# Controller_V1.net
KiCad netlist of a schematic drawn in EAGLE
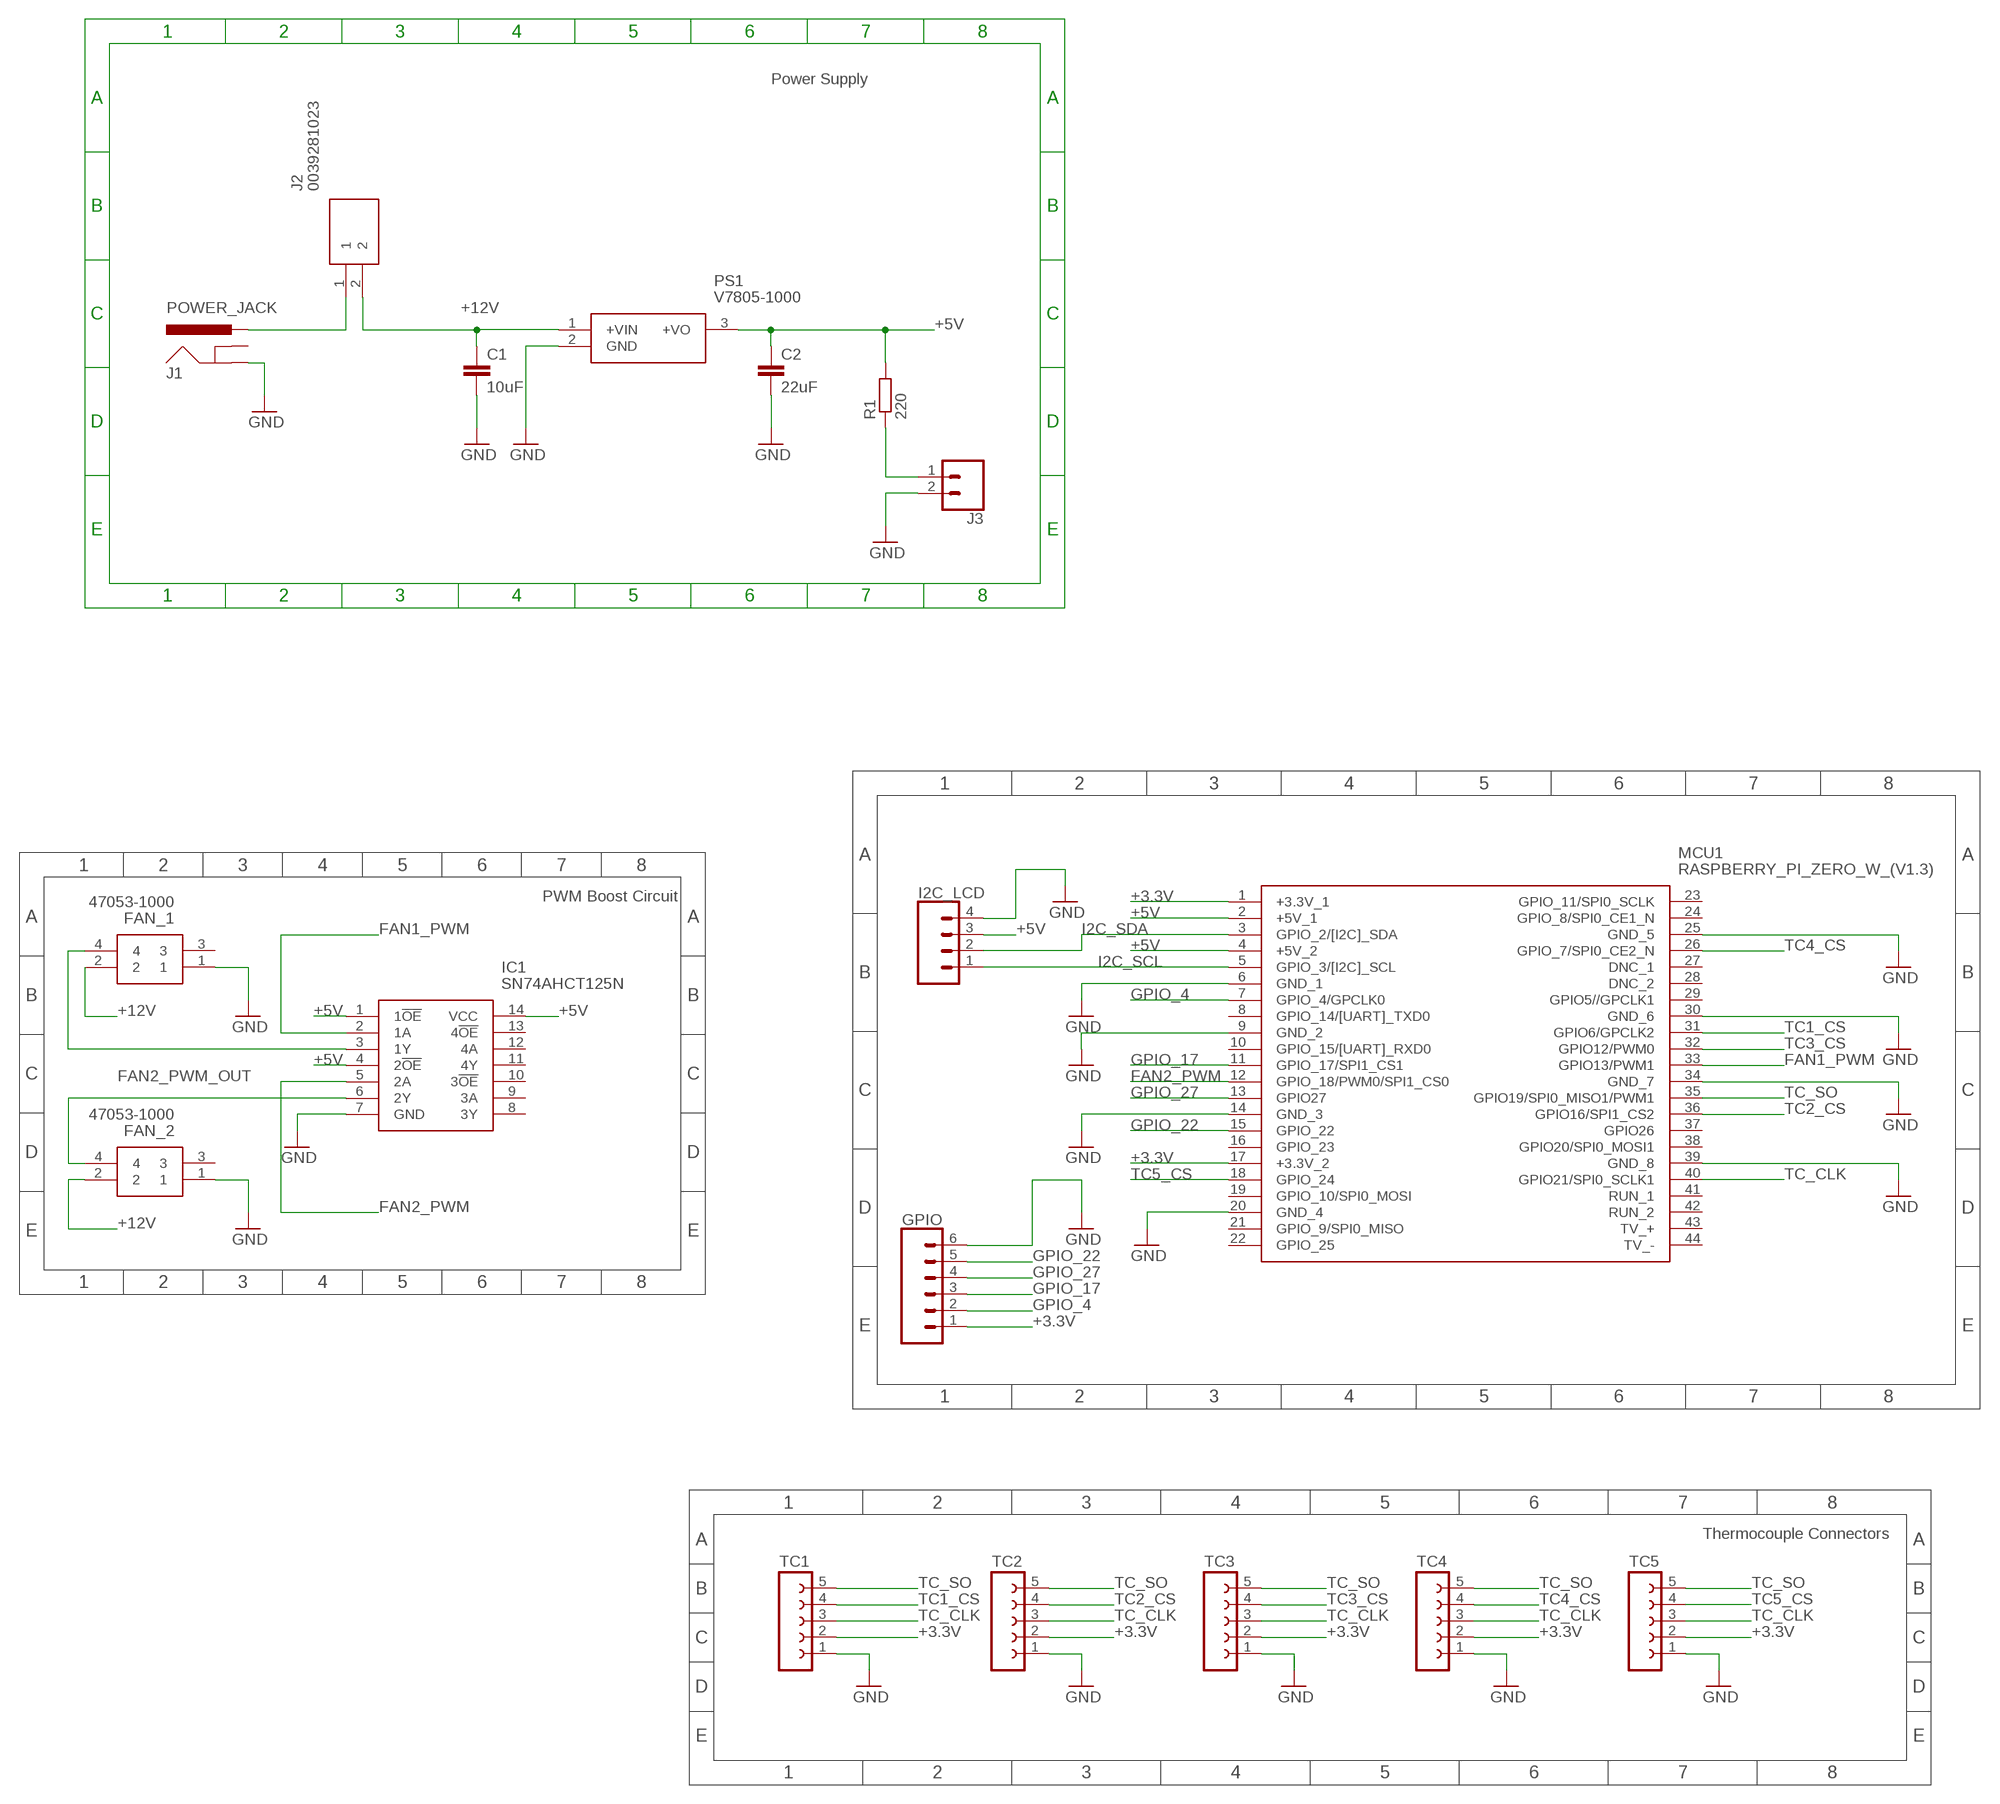
[diagram p0: schematic, sheet 1]

(export (version "E")
  (design (tool "Eeschema 10.0.6"))
  (components
    (comp (ref "C1")
      (value "10uF")
      (footprint "eagle-import:C050-024X044")
      (libsource (lib "eagle-import") (part "C-EU050-024X044"))
    )
    (comp (ref "C2")
      (value "22uF")
      (footprint "eagle-import:C050-024X044")
      (libsource (lib "eagle-import") (part "C-EU050-024X044"))
    )
    (comp (ref "FAN_1")
      (value "47053-1000")
      (footprint "eagle-import:47053-1000")
      (fields (field (name "MOUSER_PART_NUMBER") "538-47053-1000"))
      (libsource (lib "eagle-import") (part "47053-1000"))
    )
    (comp (ref "FAN_2")
      (value "47053-1000")
      (footprint "eagle-import:47053-1000")
      (fields (field (name "MOUSER_PART_NUMBER") "538-47053-1000"))
      (libsource (lib "eagle-import") (part "47053-1000"))
    )
    (comp (ref "GPIO")
      (value "CONN_06SILK_FEMALE_PTH")
      (footprint "eagle-import:1X06")
      (libsource (lib "eagle-import") (part "CONN_06SILK_FEMALE_PTH"))
    )
    (comp (ref "I2C_LCD")
      (value "CONN_04PTH")
      (footprint "eagle-import:1X04")
      (libsource (lib "eagle-import") (part "CONN_04PTH"))
    )
    (comp (ref "IC1")
      (value "SN74AHCT125N")
      (footprint "eagle-import:DIP794W53P254L1930H508Q14N")
      (fields (field (name "MOUSER_PART_NUMBER") "595-SN74AHCT125N"))
      (libsource (lib "eagle-import") (part "SN74AHCT125N"))
    )
    (comp (ref "J1")
      (value "POWER_JACK")
      (footprint "eagle-import:POWER_JACK_PTH")
      (libsource (lib "eagle-import") (part "POWER_JACK"))
    )
    (comp (ref "J2")
      (value "0039281023")
      (footprint "eagle-import:SHDR2W145P0X550_1X2_960X540X13")
      (libsource (lib "eagle-import") (part "0039281023"))
    )
    (comp (ref "J3")
      (value "CONN_02")
      (footprint "eagle-import:1X02")
      (libsource (lib "eagle-import") (part "CONN_02"))
    )
    (comp (ref "MCU1")
      (value "RASPBERRY_PI_ZERO_W_(V1.3)")
      (footprint "eagle-import:RASPBERRYPIZEROWV13")
      (fields (field (name "MANUFACTURER_PART_NUMBER") "Raspberry Pi Zero W (v1.3)"))
      (libsource (lib "eagle-import") (part "RASPBERRY_PI_ZERO_W_(V1.3)"))
    )
    (comp (ref "PS1")
      (value "V7805-1000")
      (footprint "eagle-import:V78031500")
      (fields (field (name "MOUSER_PART_NUMBER") "490-V7805-1000"))
      (libsource (lib "eagle-import") (part "V7805-1000"))
    )
    (comp (ref "R1")
      (value "220")
      (footprint "eagle-import:0309_10")
      (libsource (lib "eagle-import") (part "R-EU_0309/10"))
    )
    (comp (ref "TC1")
      (value "FE05-1")
      (footprint "eagle-import:FE05-1")
      (libsource (lib "eagle-import") (part "FE05-1"))
    )
    (comp (ref "TC2")
      (value "FE05-1")
      (footprint "eagle-import:FE05-1")
      (libsource (lib "eagle-import") (part "FE05-1"))
    )
    (comp (ref "TC3")
      (value "FE05-1")
      (footprint "eagle-import:FE05-1")
      (libsource (lib "eagle-import") (part "FE05-1"))
    )
    (comp (ref "TC4")
      (value "FE05-1")
      (footprint "eagle-import:FE05-1")
      (libsource (lib "eagle-import") (part "FE05-1"))
    )
    (comp (ref "TC5")
      (value "FE05-1")
      (footprint "eagle-import:FE05-1")
      (libsource (lib "eagle-import") (part "FE05-1"))
    )
  )
  (nets
    (net (code "1") (name "/+3.3V") (class "Default")
      (node (ref "GPIO") (pin "1") (pinfunction "1_1") (pintype "passive"))
      (node (ref "MCU1") (pin "1") (pinfunction "+3.3V_1_1") (pintype "bidirectional"))
      (node (ref "MCU1") (pin "17") (pinfunction "+3.3V_2_17") (pintype "bidirectional"))
      (node (ref "TC1") (pin "2") (pinfunction "2_2") (pintype "passive"))
      (node (ref "TC2") (pin "2") (pinfunction "2_2") (pintype "passive"))
      (node (ref "TC3") (pin "2") (pinfunction "2_2") (pintype "passive"))
      (node (ref "TC4") (pin "2") (pinfunction "2_2") (pintype "passive"))
      (node (ref "TC5") (pin "2") (pinfunction "2_2") (pintype "passive"))
    )
    (net (code "2") (name "/+5V") (class "Default")
      (node (ref "C2") (pin "1") (pinfunction "1_1") (pintype "passive"))
      (node (ref "I2C_LCD") (pin "3") (pinfunction "3_3") (pintype "passive"))
      (node (ref "IC1") (pin "1") (pinfunction "1~{OE}_1") (pintype "bidirectional"))
      (node (ref "IC1") (pin "14") (pinfunction "VCC_14") (pintype "bidirectional"))
      (node (ref "IC1") (pin "4") (pinfunction "2~{OE}_4") (pintype "bidirectional"))
      (node (ref "MCU1") (pin "2") (pinfunction "+5V_1_2") (pintype "bidirectional"))
      (node (ref "MCU1") (pin "4") (pinfunction "+5V_2_4") (pintype "bidirectional"))
      (node (ref "PS1") (pin "3") (pinfunction "+VO_3") (pintype "bidirectional"))
      (node (ref "R1") (pin "2") (pinfunction "2_2") (pintype "passive"))
    )
    (net (code "3") (name "/+12V") (class "Default")
      (node (ref "C1") (pin "1") (pinfunction "1_1") (pintype "passive"))
      (node (ref "FAN_1") (pin "2") (pinfunction "2_2") (pintype "bidirectional"))
      (node (ref "FAN_2") (pin "2") (pinfunction "2_2") (pintype "bidirectional"))
      (node (ref "J2") (pin "2") (pinfunction "2_2") (pintype "bidirectional"))
      (node (ref "PS1") (pin "1") (pinfunction "+VIN_1") (pintype "power_in"))
    )
    (net (code "4") (name "/FAN1_PWM") (class "Default")
      (node (ref "IC1") (pin "2") (pinfunction "1A_2") (pintype "bidirectional"))
      (node (ref "MCU1") (pin "33") (pinfunction "GPIO13/PWM1_33") (pintype "bidirectional"))
    )
    (net (code "5") (name "/FAN2_PWM") (class "Default")
      (node (ref "IC1") (pin "5") (pinfunction "2A_5") (pintype "bidirectional"))
      (node (ref "MCU1") (pin "12") (pinfunction "GPIO_18/PWM0/SPI1_CS0_12") (pintype "bidirectional"))
    )
    (net (code "6") (name "/FAN2_PWM_OUT") (class "Default")
      (node (ref "FAN_2") (pin "4") (pinfunction "4_4") (pintype "bidirectional"))
      (node (ref "IC1") (pin "6") (pinfunction "2Y_6") (pintype "bidirectional"))
    )
    (net (code "7") (name "/GPIO_4") (class "Default")
      (node (ref "GPIO") (pin "2") (pinfunction "2_2") (pintype "passive"))
      (node (ref "MCU1") (pin "7") (pinfunction "GPIO_4/GPCLK0_7") (pintype "bidirectional"))
    )
    (net (code "8") (name "/GPIO_17") (class "Default")
      (node (ref "GPIO") (pin "3") (pinfunction "3_3") (pintype "passive"))
      (node (ref "MCU1") (pin "11") (pinfunction "GPIO_17/SPI1_CS1_11") (pintype "bidirectional"))
    )
    (net (code "9") (name "/GPIO_22") (class "Default")
      (node (ref "GPIO") (pin "5") (pinfunction "5_5") (pintype "passive"))
      (node (ref "MCU1") (pin "15") (pinfunction "GPIO_22_15") (pintype "bidirectional"))
    )
    (net (code "10") (name "/GPIO_27") (class "Default")
      (node (ref "GPIO") (pin "4") (pinfunction "4_4") (pintype "passive"))
      (node (ref "MCU1") (pin "13") (pinfunction "GPIO27_13") (pintype "bidirectional"))
    )
    (net (code "11") (name "/I2C_SCL") (class "Default")
      (node (ref "I2C_LCD") (pin "1") (pinfunction "1_1") (pintype "passive"))
      (node (ref "MCU1") (pin "5") (pinfunction "GPIO_3/[I2C]_SCL_5") (pintype "bidirectional"))
    )
    (net (code "12") (name "/I2C_SDA") (class "Default")
      (node (ref "I2C_LCD") (pin "2") (pinfunction "2_2") (pintype "passive"))
      (node (ref "MCU1") (pin "3") (pinfunction "GPIO_2/[I2C]_SDA_3") (pintype "bidirectional"))
    )
    (net (code "13") (name "/TC1_CS") (class "Default")
      (node (ref "MCU1") (pin "31") (pinfunction "GPIO6/GPCLK2_31") (pintype "bidirectional"))
      (node (ref "TC1") (pin "4") (pinfunction "4_4") (pintype "passive"))
    )
    (net (code "14") (name "/TC2_CS") (class "Default")
      (node (ref "MCU1") (pin "36") (pinfunction "GPIO16/SPI1_CS2_36") (pintype "bidirectional"))
      (node (ref "TC2") (pin "4") (pinfunction "4_4") (pintype "passive"))
    )
    (net (code "15") (name "/TC3_CS") (class "Default")
      (node (ref "MCU1") (pin "32") (pinfunction "GPIO12/PWM0_32") (pintype "bidirectional"))
      (node (ref "TC3") (pin "4") (pinfunction "4_4") (pintype "passive"))
    )
    (net (code "16") (name "/TC4_CS") (class "Default")
      (node (ref "MCU1") (pin "26") (pinfunction "GPIO_7/SPI0_CE2_N_26") (pintype "bidirectional"))
      (node (ref "TC4") (pin "4") (pinfunction "4_4") (pintype "passive"))
    )
    (net (code "17") (name "/TC5_CS") (class "Default")
      (node (ref "MCU1") (pin "18") (pinfunction "GPIO_24_18") (pintype "bidirectional"))
      (node (ref "TC5") (pin "4") (pinfunction "4_4") (pintype "passive"))
    )
    (net (code "18") (name "/TC_CLK") (class "Default")
      (node (ref "MCU1") (pin "40") (pinfunction "GPIO21/SPI0_SCLK1_40") (pintype "bidirectional"))
      (node (ref "TC1") (pin "3") (pinfunction "3_3") (pintype "passive"))
      (node (ref "TC2") (pin "3") (pinfunction "3_3") (pintype "passive"))
      (node (ref "TC3") (pin "3") (pinfunction "3_3") (pintype "passive"))
      (node (ref "TC4") (pin "3") (pinfunction "3_3") (pintype "passive"))
      (node (ref "TC5") (pin "3") (pinfunction "3_3") (pintype "passive"))
    )
    (net (code "19") (name "/TC_SO") (class "Default")
      (node (ref "MCU1") (pin "35") (pinfunction "GPIO19/SPI0_MISO1/PWM1_35") (pintype "bidirectional"))
      (node (ref "TC1") (pin "5") (pinfunction "5_5") (pintype "passive"))
      (node (ref "TC2") (pin "5") (pinfunction "5_5") (pintype "passive"))
      (node (ref "TC3") (pin "5") (pinfunction "5_5") (pintype "passive"))
      (node (ref "TC4") (pin "5") (pinfunction "5_5") (pintype "passive"))
      (node (ref "TC5") (pin "5") (pinfunction "5_5") (pintype "passive"))
    )
    (net (code "20") (name "GND") (class "Default")
      (node (ref "C1") (pin "2") (pinfunction "2_2") (pintype "passive"))
      (node (ref "C2") (pin "2") (pinfunction "2_2") (pintype "passive"))
      (node (ref "FAN_1") (pin "1") (pinfunction "1_1") (pintype "bidirectional"))
      (node (ref "FAN_2") (pin "1") (pinfunction "1_1") (pintype "bidirectional"))
      (node (ref "GPIO") (pin "6") (pinfunction "6_6") (pintype "passive"))
      (node (ref "I2C_LCD") (pin "4") (pinfunction "4_4") (pintype "passive"))
      (node (ref "IC1") (pin "7") (pinfunction "GND_7") (pintype "bidirectional"))
      (node (ref "J1") (pin "GND") (pinfunction "GND_GND") (pintype "bidirectional"))
      (node (ref "J3") (pin "2") (pinfunction "2_2") (pintype "passive"))
      (node (ref "MCU1") (pin "14") (pinfunction "GND_3_14") (pintype "bidirectional"))
      (node (ref "MCU1") (pin "20") (pinfunction "GND_4_20") (pintype "bidirectional"))
      (node (ref "MCU1") (pin "25") (pinfunction "GND_5_25") (pintype "bidirectional"))
      (node (ref "MCU1") (pin "30") (pinfunction "GND_6_30") (pintype "bidirectional"))
      (node (ref "MCU1") (pin "34") (pinfunction "GND_7_34") (pintype "bidirectional"))
      (node (ref "MCU1") (pin "39") (pinfunction "GND_8_39") (pintype "bidirectional"))
      (node (ref "MCU1") (pin "6") (pinfunction "GND_1_6") (pintype "bidirectional"))
      (node (ref "MCU1") (pin "9") (pinfunction "GND_2_9") (pintype "bidirectional"))
      (node (ref "PS1") (pin "2") (pinfunction "GND_2") (pintype "bidirectional"))
      (node (ref "TC1") (pin "1") (pinfunction "1_1") (pintype "passive"))
      (node (ref "TC2") (pin "1") (pinfunction "1_1") (pintype "passive"))
      (node (ref "TC3") (pin "1") (pinfunction "1_1") (pintype "passive"))
      (node (ref "TC4") (pin "1") (pinfunction "1_1") (pintype "passive"))
      (node (ref "TC5") (pin "1") (pinfunction "1_1") (pintype "passive"))
    )
    (net (code "21") (name "Net-(IC1-1Y)") (class "Default")
      (node (ref "FAN_1") (pin "4") (pinfunction "4_4") (pintype "bidirectional"))
      (node (ref "IC1") (pin "3") (pinfunction "1Y_3") (pintype "bidirectional"))
    )
    (net (code "22") (name "Net-(J1-PadPWR)") (class "Default")
      (node (ref "J1") (pin "PWR") (pinfunction "PWR_PWR") (pintype "bidirectional"))
      (node (ref "J2") (pin "1") (pinfunction "1_1") (pintype "bidirectional"))
    )
    (net (code "23") (name "Net-(J3-Pad1)") (class "Default")
      (node (ref "J3") (pin "1") (pinfunction "1_1") (pintype "passive"))
      (node (ref "R1") (pin "1") (pinfunction "1_1") (pintype "passive"))
    )
    (net (code "24") (name "unconnected-(FAN_1-Pad3)") (class "Default")
      (node (ref "FAN_1") (pin "3") (pinfunction "3_3") (pintype "bidirectional"))
    )
    (net (code "25") (name "unconnected-(FAN_2-Pad3)") (class "Default")
      (node (ref "FAN_2") (pin "3") (pinfunction "3_3") (pintype "bidirectional"))
    )
    (net (code "26") (name "unconnected-(IC1-3A-Pad9)") (class "Default")
      (node (ref "IC1") (pin "9") (pinfunction "3A_9") (pintype "bidirectional"))
    )
    (net (code "27") (name "unconnected-(IC1-3Y-Pad8)") (class "Default")
      (node (ref "IC1") (pin "8") (pinfunction "3Y_8") (pintype "bidirectional"))
    )
    (net (code "28") (name "unconnected-(IC1-3~{OE}-Pad10)") (class "Default")
      (node (ref "IC1") (pin "10") (pinfunction "3~{OE}_10") (pintype "bidirectional"))
    )
    (net (code "29") (name "unconnected-(IC1-4A-Pad12)") (class "Default")
      (node (ref "IC1") (pin "12") (pinfunction "4A_12") (pintype "bidirectional"))
    )
    (net (code "30") (name "unconnected-(IC1-4Y-Pad11)") (class "Default")
      (node (ref "IC1") (pin "11") (pinfunction "4Y_11") (pintype "bidirectional"))
    )
    (net (code "31") (name "unconnected-(IC1-4~{OE}-Pad13)") (class "Default")
      (node (ref "IC1") (pin "13") (pinfunction "4~{OE}_13") (pintype "bidirectional"))
    )
    (net (code "32") (name "unconnected-(J1-PadGNDBREAK)") (class "Default")
      (node (ref "J1") (pin "GNDBREAK") (pinfunction "GNDBREAK_GNDBREAK") (pintype "bidirectional"))
    )
    (net (code "33") (name "unconnected-(MCU1-DNC_1-Pad27)") (class "Default")
      (node (ref "MCU1") (pin "27") (pinfunction "DNC_1_27") (pintype "bidirectional"))
    )
    (net (code "34") (name "unconnected-(MCU1-DNC_2-Pad28)") (class "Default")
      (node (ref "MCU1") (pin "28") (pinfunction "DNC_2_28") (pintype "bidirectional"))
    )
    (net (code "35") (name "unconnected-(MCU1-GPIO5{slash}{slash}GPCLK1-Pad29)") (class "Default")
      (node (ref "MCU1") (pin "29") (pinfunction "GPIO5//GPCLK1_29") (pintype "bidirectional"))
    )
    (net (code "36") (name "unconnected-(MCU1-GPIO20{slash}SPI0_MOSI1-Pad38)") (class "Default")
      (node (ref "MCU1") (pin "38") (pinfunction "GPIO20/SPI0_MOSI1_38") (pintype "bidirectional"))
    )
    (net (code "37") (name "unconnected-(MCU1-GPIO26-Pad37)") (class "Default")
      (node (ref "MCU1") (pin "37") (pinfunction "GPIO26_37") (pintype "bidirectional"))
    )
    (net (code "38") (name "unconnected-(MCU1-GPIO_8{slash}SPI0_CE1_N-Pad24)") (class "Default")
      (node (ref "MCU1") (pin "24") (pinfunction "GPIO_8/SPI0_CE1_N_24") (pintype "bidirectional"))
    )
    (net (code "39") (name "unconnected-(MCU1-GPIO_9{slash}SPI0_MISO-Pad21)") (class "Default")
      (node (ref "MCU1") (pin "21") (pinfunction "GPIO_9/SPI0_MISO_21") (pintype "bidirectional"))
    )
    (net (code "40") (name "unconnected-(MCU1-GPIO_10{slash}SPI0_MOSI-Pad19)") (class "Default")
      (node (ref "MCU1") (pin "19") (pinfunction "GPIO_10/SPI0_MOSI_19") (pintype "bidirectional"))
    )
    (net (code "41") (name "unconnected-(MCU1-GPIO_11{slash}SPI0_SCLK-Pad23)") (class "Default")
      (node (ref "MCU1") (pin "23") (pinfunction "GPIO_11/SPI0_SCLK_23") (pintype "bidirectional"))
    )
    (net (code "42") (name "unconnected-(MCU1-GPIO_14{slash}[UART]_TXD0-Pad8)") (class "Default")
      (node (ref "MCU1") (pin "8") (pinfunction "GPIO_14/[UART]_TXD0_8") (pintype "bidirectional"))
    )
    (net (code "43") (name "unconnected-(MCU1-GPIO_15{slash}[UART]_RXD0-Pad10)") (class "Default")
      (node (ref "MCU1") (pin "10") (pinfunction "GPIO_15/[UART]_RXD0_10") (pintype "bidirectional"))
    )
    (net (code "44") (name "unconnected-(MCU1-GPIO_23-Pad16)") (class "Default")
      (node (ref "MCU1") (pin "16") (pinfunction "GPIO_23_16") (pintype "bidirectional"))
    )
    (net (code "45") (name "unconnected-(MCU1-GPIO_25-Pad22)") (class "Default")
      (node (ref "MCU1") (pin "22") (pinfunction "GPIO_25_22") (pintype "bidirectional"))
    )
    (net (code "46") (name "unconnected-(MCU1-RUN_1-Pad41)") (class "Default")
      (node (ref "MCU1") (pin "41") (pinfunction "RUN_1_41") (pintype "bidirectional"))
    )
    (net (code "47") (name "unconnected-(MCU1-RUN_2-Pad42)") (class "Default")
      (node (ref "MCU1") (pin "42") (pinfunction "RUN_2_42") (pintype "bidirectional"))
    )
    (net (code "48") (name "unconnected-(MCU1-TV_+-Pad43)") (class "Default")
      (node (ref "MCU1") (pin "43") (pinfunction "TV_+_43") (pintype "bidirectional"))
    )
    (net (code "49") (name "unconnected-(MCU1-TV_--Pad44)") (class "Default")
      (node (ref "MCU1") (pin "44") (pinfunction "TV_-_44") (pintype "bidirectional"))
    )
  )
)
